# Power.net
KiCad netlist of a schematic drawn in Altium Designer
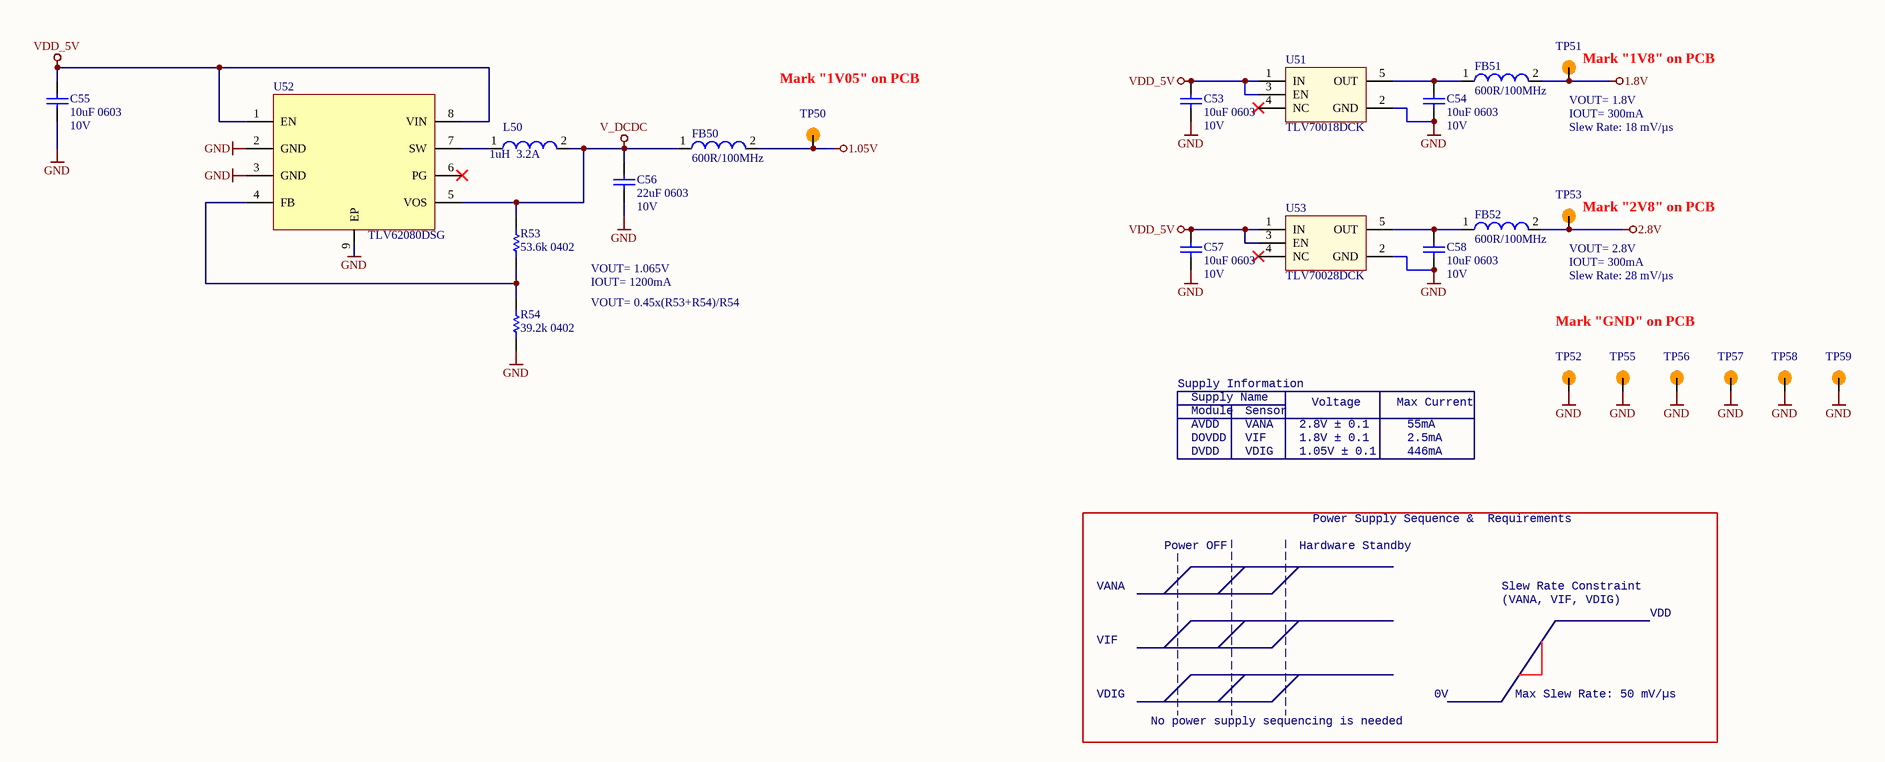
[diagram p0: Power.SchDoc]

(export (version "E")
  (design (tool "Eeschema 10.0.6"))
  (components
    (comp (ref "C53")
      (value "10uF 0603")
      (footprint "CAP_Altium_Vault_Generic:CAPC0603(1608)100_N")
      (description "CAP CER 10UF 10V X5R 0603 20%")
      (fields (field (name "TOLERANCE") "20%") (field (name "VOLTAGE RATING") "10V"))
      (libsource (lib "LuxonisMaster") (part "GRM188R61A106ME69D"))
    )
    (comp (ref "C54")
      (value "10uF 0603")
      (footprint "CAP_Altium_Vault_Generic:CAPC0603(1608)100_N")
      (description "CAP CER 10UF 10V X5R 0603 20%")
      (fields (field (name "TOLERANCE") "20%") (field (name "VOLTAGE RATING") "10V"))
      (libsource (lib "LuxonisMaster") (part "GRM188R61A106ME69D"))
    )
    (comp (ref "C55")
      (value "10uF 0603")
      (footprint "CAP_Altium_Vault_Generic:CAPC0603(1608)100_N")
      (description "CAP CER 10UF 10V X5R 0603 20%")
      (fields (field (name "TOLERANCE") "20%") (field (name "VOLTAGE RATING") "10V"))
      (libsource (lib "LuxonisMaster") (part "GRM188R61A106ME69D"))
    )
    (comp (ref "C56")
      (value "22uF 0603")
      (footprint "CAP_Altium_Vault_Generic:CAPC0603(1608)100_N")
      (description "CAP CER 22UF 10V X5R 0603 20%")
      (fields (field (name "TOLERANCE") "20%") (field (name "VOLTAGE RATING") "10V"))
      (libsource (lib "LuxonisMaster") (part "GRM188R61A226ME15D"))
    )
    (comp (ref "C57")
      (value "10uF 0603")
      (footprint "CAP_Altium_Vault_Generic:CAPC0603(1608)100_N")
      (description "CAP CER 10UF 10V X5R 0603 20%")
      (fields (field (name "TOLERANCE") "20%") (field (name "VOLTAGE RATING") "10V"))
      (libsource (lib "LuxonisMaster") (part "GRM188R61A106ME69D"))
    )
    (comp (ref "C58")
      (value "10uF 0603")
      (footprint "CAP_Altium_Vault_Generic:CAPC0603(1608)100_N")
      (description "CAP CER 10UF 10V X5R 0603 20%")
      (fields (field (name "TOLERANCE") "20%") (field (name "VOLTAGE RATING") "10V"))
      (libsource (lib "LuxonisMaster") (part "GRM188R61A106ME69D"))
    )
    (comp (ref "FB50")
      (value "600R/100MHz")
      (footprint "LuxonisMaster:2508056017Y2")
      (description "FERRITE BEAD, 0.1OHM, 2A, 0805, 600R/100MHz")
      (fields (field (name "TOLERANCE") "25%"))
      (libsource (lib "LuxonisMaster") (part "2508056017Y2"))
    )
    (comp (ref "FB51")
      (value "600R/100MHz")
      (footprint "LuxonisMaster:2508056017Y2")
      (description "FERRITE BEAD, 0.1OHM, 2A, 0805, 600R/100MHz")
      (fields (field (name "TOLERANCE") "25%"))
      (libsource (lib "LuxonisMaster") (part "2508056017Y2"))
    )
    (comp (ref "FB52")
      (value "600R/100MHz")
      (footprint "LuxonisMaster:2508056017Y2")
      (description "FERRITE BEAD, 0.1OHM, 2A, 0805, 600R/100MHz")
      (fields (field (name "TOLERANCE") "25%"))
      (libsource (lib "LuxonisMaster") (part "2508056017Y2"))
    )
    (comp (ref "L50")
      (value "1uH, 3.2A, 20%")
      (footprint "LuxonisMaster:DFE252012P-1R0M=P2")
      (description "FIXED IND 1UH 3.2A 42 MOHM SMD")
      (fields
        (field (name "MANUFACTURER") "Murata")
        (field (name "MANUFACTURER PART NUMBER") "DFE252012P-1R0M=P2")
        (field (name "MAX DC CURRENT") "3.2A")
        (field (name "INDUCTANCE") "1uH")
      )
      (libsource (lib "LuxonisMaster") (part "DFE252012P-1R0M=P2"))
    )
    (comp (ref "R53")
      (value "53.6k 0402")
      (footprint "RES_Altium_Vault_Generic:RESC0402(1005)_N")
      (description "RES SMD 53.6K OHM 1% 1/16W 0402")
      (fields (field (name "TOLERANCE") "1%"))
      (libsource (lib "LuxonisMaster") (part "CRCW040253K6FKED"))
    )
    (comp (ref "R54")
      (value "39.2k 0402")
      (footprint "RES_Altium_Vault_Generic:RESC0402(1005)_N")
      (description "RES SMD 39.2K OHM 1% 1/16W 0402")
      (fields (field (name "TOLERANCE") "1%"))
      (libsource (lib "LuxonisMaster") (part "CRCW040239K2FKED"))
    )
    (comp (ref "TP50")
      (value "TP100_150_NS")
      (footprint "LuxonisMaster:TP100_150_NS")
      (libsource (lib "LuxonisMaster") (part "TEST_POINT"))
    )
    (comp (ref "TP51")
      (value "TP100_150_NS")
      (footprint "LuxonisMaster:TP100_150_NS")
      (libsource (lib "LuxonisMaster") (part "TEST_POINT"))
    )
    (comp (ref "TP52")
      (value "TP100_150_NS")
      (footprint "LuxonisMaster:TP100_150_NS")
      (libsource (lib "LuxonisMaster") (part "TEST_POINT"))
    )
    (comp (ref "TP53")
      (value "TP100_150_NS")
      (footprint "LuxonisMaster:TP100_150_NS")
      (libsource (lib "LuxonisMaster") (part "TEST_POINT"))
    )
    (comp (ref "TP55")
      (value "TP100_150_NS")
      (footprint "LuxonisMaster:TP100_150_NS")
      (libsource (lib "LuxonisMaster") (part "TEST_POINT"))
    )
    (comp (ref "TP56")
      (value "TP100_150_NS")
      (footprint "LuxonisMaster:TP100_150_NS")
      (libsource (lib "LuxonisMaster") (part "TEST_POINT"))
    )
    (comp (ref "TP57")
      (value "TP100_150_NS")
      (footprint "LuxonisMaster:TP100_150_NS")
      (libsource (lib "LuxonisMaster") (part "TEST_POINT"))
    )
    (comp (ref "TP58")
      (value "TP100_150_NS")
      (footprint "LuxonisMaster:TP100_150_NS")
      (libsource (lib "LuxonisMaster") (part "TEST_POINT"))
    )
    (comp (ref "TP59")
      (value "TP100_150_NS")
      (footprint "LuxonisMaster:TP100_150_NS")
      (libsource (lib "LuxonisMaster") (part "TEST_POINT"))
    )
    (comp (ref "U51")
      (value "TLV70018DCK")
      (footprint "LuxonisMaster:TLV70018DCK")
      (description "IC REG LINEAR 1.8V 200MA SC70-5 Linear Voltage Regulator IC  1 Output  200mA SC-70-5")
      (libsource (lib "LuxonisMaster") (part "TLV70018DCK"))
    )
    (comp (ref "U52")
      (value "TLV62080DSG")
      (footprint "LuxonisMaster:TLV62080DSG")
      (description "IC REG BUCK ADJ 1.2A SYNC 8WSON")
      (libsource (lib "LuxonisMaster") (part "TLV62080DSG"))
    )
    (comp (ref "U53")
      (value "TLV70028DCK")
      (footprint "LuxonisMaster:TLV70028DCK")
      (description "IC REG LINEAR 2.8V 200MA SC70-5 Linear Voltage Regulator IC  1 Output  200mA SC-70-5")
      (libsource (lib "LuxonisMaster") (part "TLV70028DCK"))
    )
  )
  (nets
    (net (code "1") (name "1.05V") (class "Default")
      (node (ref "FB50") (pin "2") (pinfunction "2_2") (pintype "passive"))
      (node (ref "TP50") (pin "1") (pintype "passive"))
    )
    (net (code "2") (name "1.8V") (class "Default")
      (node (ref "FB51") (pin "2") (pinfunction "2_2") (pintype "passive"))
      (node (ref "TP51") (pin "1") (pintype "passive"))
    )
    (net (code "3") (name "2.8V") (class "Default")
      (node (ref "FB52") (pin "2") (pinfunction "2_2") (pintype "passive"))
      (node (ref "TP53") (pin "1") (pintype "passive"))
    )
    (net (code "4") (name "GND") (class "Default")
      (node (ref "C53") (pin "1") (pinfunction "1_1") (pintype "passive"))
      (node (ref "C54") (pin "1") (pinfunction "1_1") (pintype "passive"))
      (node (ref "C55") (pin "1") (pinfunction "1_1") (pintype "passive"))
      (node (ref "C56") (pin "1") (pinfunction "1_1") (pintype "passive"))
      (node (ref "C57") (pin "1") (pinfunction "1_1") (pintype "passive"))
      (node (ref "C58") (pin "1") (pinfunction "1_1") (pintype "passive"))
      (node (ref "R54") (pin "1") (pinfunction "1_1") (pintype "passive"))
      (node (ref "TP52") (pin "1") (pintype "passive"))
      (node (ref "TP55") (pin "1") (pintype "passive"))
      (node (ref "TP56") (pin "1") (pintype "passive"))
      (node (ref "TP57") (pin "1") (pintype "passive"))
      (node (ref "TP58") (pin "1") (pintype "passive"))
      (node (ref "TP59") (pin "1") (pintype "passive"))
      (node (ref "U51") (pin "2") (pinfunction "GND_2") (pintype "passive"))
      (node (ref "U52") (pin "2") (pinfunction "GND_2") (pintype "passive"))
      (node (ref "U52") (pin "3") (pinfunction "GND_3") (pintype "passive"))
      (node (ref "U52") (pin "9") (pinfunction "EP_9") (pintype "passive"))
      (node (ref "U53") (pin "2") (pinfunction "GND_2") (pintype "passive"))
    )
    (net (code "5") (name "Net-(U51-OUT)") (class "Default")
      (node (ref "C54") (pin "2") (pinfunction "2_2") (pintype "passive"))
      (node (ref "FB51") (pin "1") (pinfunction "1_1") (pintype "passive"))
      (node (ref "U51") (pin "5") (pinfunction "OUT_5") (pintype "passive"))
    )
    (net (code "6") (name "Net-(U52-FB)") (class "Default")
      (node (ref "R53") (pin "1") (pinfunction "1_1") (pintype "passive"))
      (node (ref "R54") (pin "2") (pinfunction "2_2") (pintype "passive"))
      (node (ref "U52") (pin "4") (pinfunction "FB_4") (pintype "passive"))
    )
    (net (code "7") (name "Net-(U52-SW)") (class "Default")
      (node (ref "L50") (pin "1") (pinfunction "1_1") (pintype "passive"))
      (node (ref "U52") (pin "7") (pinfunction "SW_7") (pintype "passive"))
    )
    (net (code "8") (name "Net-(U53-OUT)") (class "Default")
      (node (ref "C58") (pin "2") (pinfunction "2_2") (pintype "passive"))
      (node (ref "FB52") (pin "1") (pinfunction "1_1") (pintype "passive"))
      (node (ref "U53") (pin "5") (pinfunction "OUT_5") (pintype "passive"))
    )
    (net (code "9") (name "VDD_5V") (class "Default")
      (node (ref "C53") (pin "2") (pinfunction "2_2") (pintype "passive"))
      (node (ref "C55") (pin "2") (pinfunction "2_2") (pintype "passive"))
      (node (ref "C57") (pin "2") (pinfunction "2_2") (pintype "passive"))
      (node (ref "U51") (pin "1") (pinfunction "IN_1") (pintype "passive"))
      (node (ref "U51") (pin "3") (pinfunction "EN_3") (pintype "passive"))
      (node (ref "U52") (pin "1") (pinfunction "EN_1") (pintype "passive"))
      (node (ref "U52") (pin "8") (pinfunction "VIN_8") (pintype "passive"))
      (node (ref "U53") (pin "1") (pinfunction "IN_1") (pintype "passive"))
      (node (ref "U53") (pin "3") (pinfunction "EN_3") (pintype "passive"))
    )
    (net (code "10") (name "V_DCDC") (class "Default")
      (node (ref "C56") (pin "2") (pinfunction "2_2") (pintype "passive"))
      (node (ref "FB50") (pin "1") (pinfunction "1_1") (pintype "passive"))
      (node (ref "L50") (pin "2") (pinfunction "2_2") (pintype "passive"))
      (node (ref "R53") (pin "2") (pinfunction "2_2") (pintype "passive"))
      (node (ref "U52") (pin "5") (pinfunction "VOS_5") (pintype "passive"))
    )
    (net (code "11") (name "unconnected-(U51-NC-Pad4)") (class "Default")
      (node (ref "U51") (pin "4") (pinfunction "NC_4") (pintype "passive+no_connect"))
    )
    (net (code "12") (name "unconnected-(U52-PG-Pad6)") (class "Default")
      (node (ref "U52") (pin "6") (pinfunction "PG_6") (pintype "passive+no_connect"))
    )
    (net (code "13") (name "unconnected-(U53-NC-Pad4)") (class "Default")
      (node (ref "U53") (pin "4") (pinfunction "NC_4") (pintype "passive+no_connect"))
    )
  )
)
